# Thermocouple.net
KiCad netlist of a schematic drawn in Altium Designer
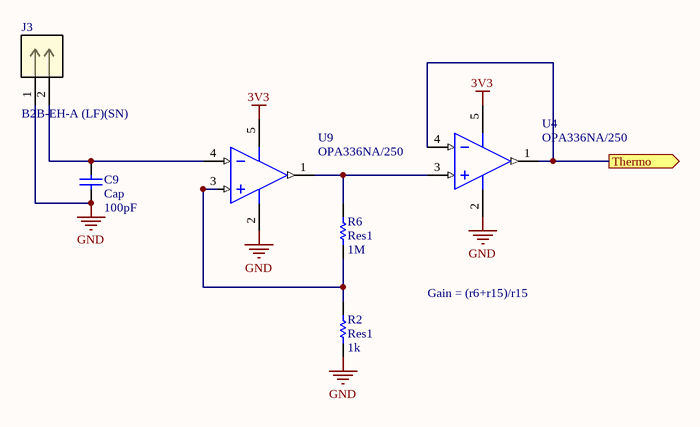
[diagram p0: Thermocouple.SchDoc]

(export (version "E")
  (design (tool "Eeschema 10.0.6"))
  (components
    (comp (ref "C9")
      (value "Cap")
      (footprint "0402-A")
      (description "Capacitor")
      (fields (field (name "ALTIUM_VALUE") "100pF") (field (name "PUBLISHER") "Altium Limited"))
      (libsource (lib "Miscellaneous Devices") (part "Cap"))
    )
    (comp (ref "J3")
      (value "B2B-EH-A (LF)(SN)")
      (footprint "CONN_B2B-EH-A (LF)(SN)_JST")
      (description "No Description Available")
      (fields (field (name "COPYRIGHT") "Copyright (C) 2018 Accelerated Designs. All rights reserved"))
      (libsource (lib "2020-09-22_22-27-35") (part "B2B-EH-A (LF)(SN)"))
    )
    (comp (ref "R2")
      (value "Res1")
      (footprint "0402-A")
      (description "Resistor")
      (fields (field (name "ALTIUM_VALUE") "1k") (field (name "PUBLISHER") "Altium Limited"))
      (libsource (lib "Miscellaneous Devices") (part "Res1"))
    )
    (comp (ref "R6")
      (value "Res1")
      (footprint "0402-A")
      (description "Resistor")
      (fields (field (name "ALTIUM_VALUE") "1M") (field (name "PUBLISHER") "Altium Limited"))
      (libsource (lib "Miscellaneous Devices") (part "Res1"))
    )
    (comp (ref "U4")
      (value "OPA336NA/250")
      (footprint "DBV0005A_M")
      (fields (field (name "MANUFACTURER") "Texas Instruments"))
      (libsource (lib "Altium Content Vault") (part "TI-OPA_SM7XXXX-DBV5"))
    )
    (comp (ref "U9")
      (value "OPA336NA/250")
      (footprint "DBV0005A_M")
      (fields (field (name "MANUFACTURER") "Texas Instruments"))
      (libsource (lib "Altium Content Vault") (part "TI-OPA_SM7XXXX-DBV5"))
    )
  )
  (nets
    (net (code "1") (name "/Thermo") (class "Default")
      (node (ref "U4") (pin "1") (pinfunction "OUT_1") (pintype "output"))
      (node (ref "U4") (pin "4") (pinfunction "IN-_4") (pintype "input"))
    )
    (net (code "2") (name "3V3") (class "Default")
      (node (ref "U4") (pin "5") (pinfunction "V+_5") (pintype "power_in"))
      (node (ref "U9") (pin "5") (pinfunction "V+_5") (pintype "power_in"))
    )
    (net (code "3") (name "GND") (class "Default")
      (node (ref "C9") (pin "1") (pinfunction "1_1") (pintype "passive"))
      (node (ref "J3") (pin "1") (pinfunction "1_1") (pintype "passive"))
      (node (ref "R2") (pin "2") (pinfunction "2_2") (pintype "passive"))
      (node (ref "U4") (pin "2") (pinfunction "V-_2") (pintype "power_in"))
      (node (ref "U9") (pin "2") (pinfunction "V-_2") (pintype "power_in"))
    )
    (net (code "4") (name "Net-(U4-IN+)") (class "Default")
      (node (ref "R6") (pin "1") (pinfunction "1_1") (pintype "passive"))
      (node (ref "U4") (pin "3") (pinfunction "IN+_3") (pintype "input"))
      (node (ref "U9") (pin "1") (pinfunction "OUT_1") (pintype "output"))
    )
    (net (code "5") (name "Net-(U9-IN+)") (class "Default")
      (node (ref "R2") (pin "1") (pinfunction "1_1") (pintype "passive"))
      (node (ref "R6") (pin "2") (pinfunction "2_2") (pintype "passive"))
      (node (ref "U9") (pin "3") (pinfunction "IN+_3") (pintype "input"))
    )
    (net (code "6") (name "Net-(U9-IN-)") (class "Default")
      (node (ref "C9") (pin "2") (pinfunction "2_2") (pintype "passive"))
      (node (ref "J3") (pin "2") (pinfunction "2_2") (pintype "passive"))
      (node (ref "U9") (pin "4") (pinfunction "IN-_4") (pintype "input"))
    )
  )
)
